# ublisterred_vow.net
KiCad netlist of a schematic drawn in EAGLE
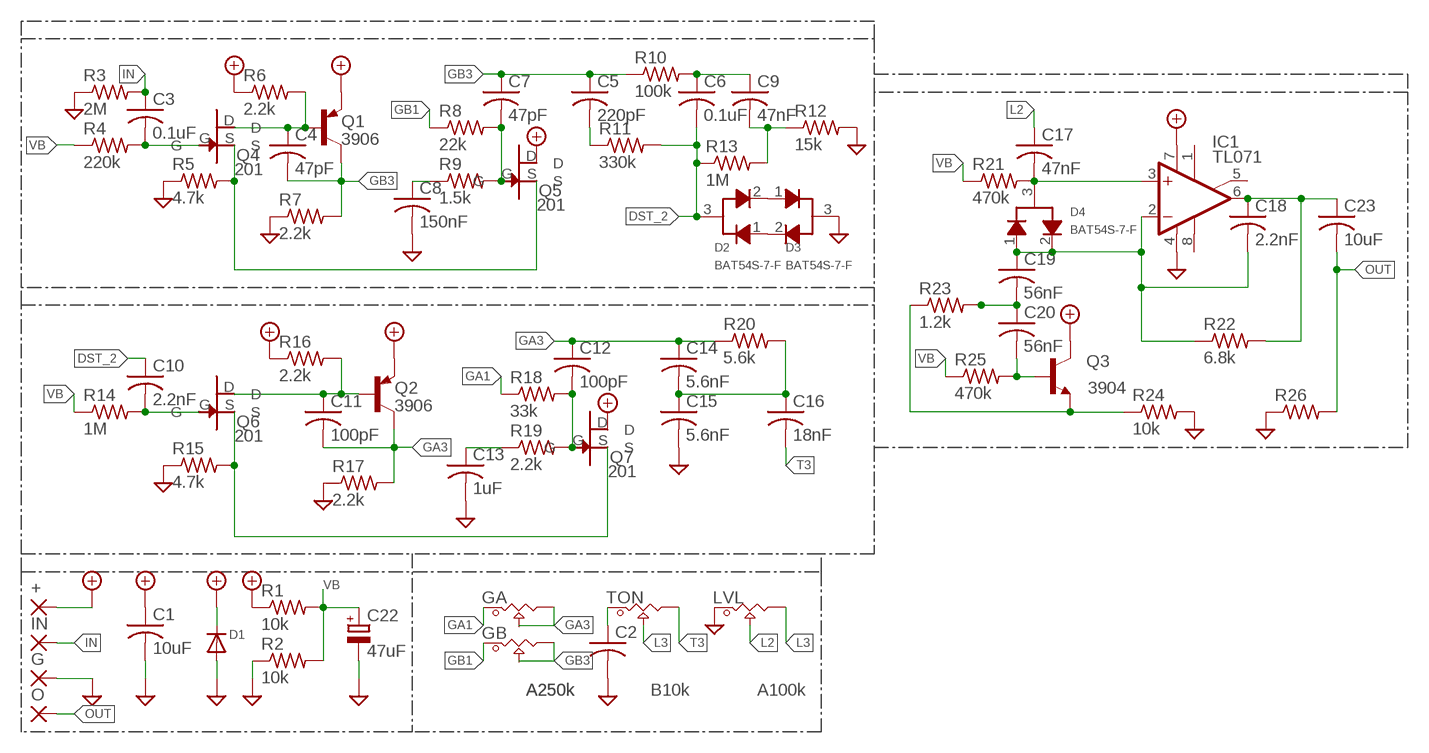
[diagram p0: schematic, sheet 1]

(export (version "E")
  (design (tool "Eeschema 10.0.6"))
  (components
    (comp (ref "+")
      (value "SMD2")
      (footprint "eagle-import:SMD1,27-2,54")
      (libsource (lib "eagle-import") (part "SMD2"))
    )
    (comp (ref "C1")
      (value "10uF")
      (footprint "eagle-import:C1206")
      (libsource (lib "eagle-import") (part "adafruit_420_C-USC1206"))
    )
    (comp (ref "C2")
      (value "C-USC0603")
      (footprint "eagle-import:C0603")
      (libsource (lib "eagle-import") (part "C-USC0603"))
    )
    (comp (ref "C3")
      (value "0.1uF")
      (footprint "eagle-import:C0603")
      (libsource (lib "eagle-import") (part "C-USC0603"))
    )
    (comp (ref "C4")
      (value "47pF")
      (footprint "eagle-import:C0603")
      (libsource (lib "eagle-import") (part "C-USC0603"))
    )
    (comp (ref "C5")
      (value "220pF")
      (footprint "eagle-import:C0603")
      (libsource (lib "eagle-import") (part "C-USC0603"))
    )
    (comp (ref "C6")
      (value "0.1uF")
      (footprint "eagle-import:C0603")
      (libsource (lib "eagle-import") (part "C-USC0603"))
    )
    (comp (ref "C7")
      (value "47pF")
      (footprint "eagle-import:C0603")
      (libsource (lib "eagle-import") (part "C-USC0603"))
    )
    (comp (ref "C8")
      (value "150nF")
      (footprint "eagle-import:C0603")
      (libsource (lib "eagle-import") (part "C-USC0603"))
    )
    (comp (ref "C9")
      (value "47nF")
      (footprint "eagle-import:C0603")
      (libsource (lib "eagle-import") (part "C-USC0603"))
    )
    (comp (ref "C10")
      (value "2.2nF")
      (footprint "eagle-import:C0603")
      (libsource (lib "eagle-import") (part "C-USC0603"))
    )
    (comp (ref "C11")
      (value "100pF")
      (footprint "eagle-import:C0603")
      (libsource (lib "eagle-import") (part "C-USC0603"))
    )
    (comp (ref "C12")
      (value "100pF")
      (footprint "eagle-import:C0603")
      (libsource (lib "eagle-import") (part "C-USC0603"))
    )
    (comp (ref "C13")
      (value "1uF")
      (footprint "eagle-import:C0603")
      (libsource (lib "eagle-import") (part "C-USC0603"))
    )
    (comp (ref "C14")
      (value "5.6nF")
      (footprint "eagle-import:C0603")
      (libsource (lib "eagle-import") (part "C-USC0603"))
    )
    (comp (ref "C15")
      (value "5.6nF")
      (footprint "eagle-import:C0603")
      (libsource (lib "eagle-import") (part "C-USC0603"))
    )
    (comp (ref "C16")
      (value "18nF")
      (footprint "eagle-import:C0603")
      (libsource (lib "eagle-import") (part "C-USC0603"))
    )
    (comp (ref "C17")
      (value "47nF")
      (footprint "eagle-import:C0603")
      (libsource (lib "eagle-import") (part "C-USC0603"))
    )
    (comp (ref "C18")
      (value "2.2nF")
      (footprint "eagle-import:C0603")
      (libsource (lib "eagle-import") (part "C-USC0603"))
    )
    (comp (ref "C19")
      (value "56nF")
      (footprint "eagle-import:C0603")
      (libsource (lib "eagle-import") (part "C-USC0603"))
    )
    (comp (ref "C20")
      (value "56nF")
      (footprint "eagle-import:C0603")
      (libsource (lib "eagle-import") (part "C-USC0603"))
    )
    (comp (ref "C22")
      (value "47uF")
      (footprint "eagle-import:CAPMP7343X310N")
      (libsource (lib "eagle-import") (part "C-POLTANTALUM-2917(7343-METRIC)_"))
    )
    (comp (ref "C23")
      (value "10uF")
      (footprint "eagle-import:C1206")
      (libsource (lib "eagle-import") (part "adafruit_420_C-USC1206"))
    )
    (comp (ref "D1")
      (value "DIODESOD-123")
      (footprint "eagle-import:SOD-123")
      (libsource (lib "eagle-import") (part "DIODESOD-123"))
    )
    (comp (ref "D2")
      (value "BAT54S-7-F")
      (footprint "eagle-import:SOT23-3")
      (fields
        (field (name "DIGIKEY_PART_NUMBER") "BAT54S-FDITR-ND")
        (field (name "MANUFACTURER") "Diodes Incorporated")
        (field (name "CREATED_BY") "PCBLayout.com")
      )
      (libsource (lib "eagle-import") (part "BAT54S-7-F"))
    )
    (comp (ref "D3")
      (value "BAT54S-7-F")
      (footprint "eagle-import:SOT23-3")
      (fields
        (field (name "DIGIKEY_PART_NUMBER") "BAT54S-FDITR-ND")
        (field (name "MANUFACTURER") "Diodes Incorporated")
        (field (name "CREATED_BY") "PCBLayout.com")
      )
      (libsource (lib "eagle-import") (part "BAT54S-7-F"))
    )
    (comp (ref "D4")
      (value "BAT54S-7-F")
      (footprint "eagle-import:SOT23-3")
      (fields
        (field (name "DIGIKEY_PART_NUMBER") "BAT54S-FDITR-ND")
        (field (name "MANUFACTURER") "Diodes Incorporated")
        (field (name "CREATED_BY") "PCBLayout.com")
      )
      (libsource (lib "eagle-import") (part "BAT54S-7-F"))
    )
    (comp (ref "G")
      (value "SMD2")
      (footprint "eagle-import:SMD1,27-2,54")
      (libsource (lib "eagle-import") (part "SMD2"))
    )
    (comp (ref "GA")
      (value "A250k")
      (footprint "eagle-import:POT_9MM_SMD")
      (libsource (lib "eagle-import") (part "POT_9MM_SMD"))
    )
    (comp (ref "GB")
      (value "A250k")
      (footprint "eagle-import:POT_9MM_SMD")
      (libsource (lib "eagle-import") (part "POT_9MM_SMD"))
    )
    (comp (ref "IC1")
      (value "TL071")
      (footprint "eagle-import:SO08")
      (libsource (lib "eagle-import") (part "TL071D"))
    )
    (comp (ref "IN")
      (value "SMD2")
      (footprint "eagle-import:SMD1,27-2,54")
      (libsource (lib "eagle-import") (part "SMD2"))
    )
    (comp (ref "LVL")
      (value "A100k")
      (footprint "eagle-import:POT_9MM_SMD")
      (libsource (lib "eagle-import") (part "POT_9MM_SMD"))
    )
    (comp (ref "O")
      (value "SMD2")
      (footprint "eagle-import:SMD1,27-2,54")
      (libsource (lib "eagle-import") (part "SMD2"))
    )
    (comp (ref "Q1")
      (value "3906")
      (footprint "eagle-import:SOT23-3")
      (fields
        (field (name "MANUFACTURER") "ON Semiconductor")
        (field (name "MPN") "MMBT3906LT1G")
        (field (name "CREATED_BY") "PCBLayout.com")
      )
      (libsource (lib "eagle-import") (part "MMBT3906LT1G"))
    )
    (comp (ref "Q2")
      (value "3906")
      (footprint "eagle-import:SOT23-3")
      (fields
        (field (name "MANUFACTURER") "ON Semiconductor")
        (field (name "MPN") "MMBT3906LT1G")
        (field (name "CREATED_BY") "PCBLayout.com")
      )
      (libsource (lib "eagle-import") (part "MMBT3906LT1G"))
    )
    (comp (ref "Q3")
      (value "3904")
      (footprint "eagle-import:SOT23-3")
      (fields
        (field (name "DIGIKEY_PART_NUMBER") "MMBT3904LT1GOSTR-ND")
        (field (name "MANUFACTURER") "ON Semiconductor")
        (field (name "MPN") "MMBT3904LT1G")
        (field (name "CREATED_BY") "PCBLayout.com")
      )
      (libsource (lib "eagle-import") (part "MMBT3904LT1G"))
    )
    (comp (ref "Q4")
      (value "201")
      (footprint "eagle-import:MMBFJ201")
      (libsource (lib "eagle-import") (part "MMBFJ201"))
    )
    (comp (ref "Q5")
      (value "201")
      (footprint "eagle-import:MMBFJ201")
      (libsource (lib "eagle-import") (part "MMBFJ201"))
    )
    (comp (ref "Q6")
      (value "201")
      (footprint "eagle-import:MMBFJ201")
      (libsource (lib "eagle-import") (part "MMBFJ201"))
    )
    (comp (ref "Q7")
      (value "201")
      (footprint "eagle-import:MMBFJ201")
      (libsource (lib "eagle-import") (part "MMBFJ201"))
    )
    (comp (ref "R1")
      (value "10k")
      (footprint "eagle-import:R0603")
      (libsource (lib "eagle-import") (part "R-US_R0603"))
    )
    (comp (ref "R2")
      (value "10k")
      (footprint "eagle-import:R0603")
      (libsource (lib "eagle-import") (part "R-US_R0603"))
    )
    (comp (ref "R3")
      (value "2M")
      (footprint "eagle-import:R0603")
      (libsource (lib "eagle-import") (part "R-US_R0603"))
    )
    (comp (ref "R4")
      (value "220k")
      (footprint "eagle-import:R0603")
      (libsource (lib "eagle-import") (part "R-US_R0603"))
    )
    (comp (ref "R5")
      (value "4.7k")
      (footprint "eagle-import:R0603")
      (libsource (lib "eagle-import") (part "R-US_R0603"))
    )
    (comp (ref "R6")
      (value "2.2k")
      (footprint "eagle-import:R0603")
      (libsource (lib "eagle-import") (part "R-US_R0603"))
    )
    (comp (ref "R7")
      (value "2.2k")
      (footprint "eagle-import:R0603")
      (libsource (lib "eagle-import") (part "R-US_R0603"))
    )
    (comp (ref "R8")
      (value "22k")
      (footprint "eagle-import:R0603")
      (libsource (lib "eagle-import") (part "R-US_R0603"))
    )
    (comp (ref "R9")
      (value "1.5k")
      (footprint "eagle-import:R0603")
      (libsource (lib "eagle-import") (part "R-US_R0603"))
    )
    (comp (ref "R10")
      (value "100k")
      (footprint "eagle-import:R0603")
      (libsource (lib "eagle-import") (part "R-US_R0603"))
    )
    (comp (ref "R11")
      (value "330k")
      (footprint "eagle-import:R0603")
      (libsource (lib "eagle-import") (part "R-US_R0603"))
    )
    (comp (ref "R12")
      (value "15k")
      (footprint "eagle-import:R0603")
      (libsource (lib "eagle-import") (part "R-US_R0603"))
    )
    (comp (ref "R13")
      (value "1M")
      (footprint "eagle-import:R0603")
      (libsource (lib "eagle-import") (part "R-US_R0603"))
    )
    (comp (ref "R14")
      (value "1M")
      (footprint "eagle-import:R0603")
      (libsource (lib "eagle-import") (part "R-US_R0603"))
    )
    (comp (ref "R15")
      (value "4.7k")
      (footprint "eagle-import:R0603")
      (libsource (lib "eagle-import") (part "R-US_R0603"))
    )
    (comp (ref "R16")
      (value "2.2k")
      (footprint "eagle-import:R0603")
      (libsource (lib "eagle-import") (part "R-US_R0603"))
    )
    (comp (ref "R17")
      (value "2.2k")
      (footprint "eagle-import:R0603")
      (libsource (lib "eagle-import") (part "R-US_R0603"))
    )
    (comp (ref "R18")
      (value "33k")
      (footprint "eagle-import:R0603")
      (libsource (lib "eagle-import") (part "R-US_R0603"))
    )
    (comp (ref "R19")
      (value "2.2k")
      (footprint "eagle-import:R0603")
      (libsource (lib "eagle-import") (part "R-US_R0603"))
    )
    (comp (ref "R20")
      (value "5.6k")
      (footprint "eagle-import:R0603")
      (libsource (lib "eagle-import") (part "R-US_R0603"))
    )
    (comp (ref "R21")
      (value "470k")
      (footprint "eagle-import:R0603")
      (libsource (lib "eagle-import") (part "R-US_R0603"))
    )
    (comp (ref "R22")
      (value "6.8k")
      (footprint "eagle-import:R0603")
      (libsource (lib "eagle-import") (part "R-US_R0603"))
    )
    (comp (ref "R23")
      (value "1.2k")
      (footprint "eagle-import:R0603")
      (libsource (lib "eagle-import") (part "R-US_R0603"))
    )
    (comp (ref "R24")
      (value "10k")
      (footprint "eagle-import:R0603")
      (libsource (lib "eagle-import") (part "R-US_R0603"))
    )
    (comp (ref "R25")
      (value "470k")
      (footprint "eagle-import:R0603")
      (libsource (lib "eagle-import") (part "R-US_R0603"))
    )
    (comp (ref "R26")
      (value "R-US_R0603")
      (footprint "eagle-import:R0603")
      (libsource (lib "eagle-import") (part "R-US_R0603"))
    )
    (comp (ref "TON")
      (value "B10k")
      (footprint "eagle-import:POT_9MM_SMD")
      (libsource (lib "eagle-import") (part "POT_9MM_SMD"))
    )
  )
  (nets
    (net (code "1") (name "+9V") (class "Default")
      (node (ref "+") (pin "1") (pinfunction "P_1") (pintype "passive"))
      (node (ref "C1") (pin "1") (pinfunction "1_1") (pintype "passive"))
      (node (ref "D1") (pin "C") (pinfunction "C_C") (pintype "passive"))
      (node (ref "IC1") (pin "7") (pinfunction "V+_7") (pintype "power_in"))
      (node (ref "Q1") (pin "2") (pinfunction "E_2") (pintype "passive"))
      (node (ref "Q2") (pin "2") (pinfunction "E_2") (pintype "passive"))
      (node (ref "Q3") (pin "3") (pinfunction "C_3") (pintype "passive"))
      (node (ref "Q5") (pin "D") (pinfunction "D_D") (pintype "bidirectional"))
      (node (ref "Q7") (pin "D") (pinfunction "D_D") (pintype "bidirectional"))
      (node (ref "R1") (pin "1") (pinfunction "1_1") (pintype "passive"))
      (node (ref "R16") (pin "1") (pinfunction "1_1") (pintype "passive"))
      (node (ref "R6") (pin "1") (pinfunction "1_1") (pintype "passive"))
    )
    (net (code "2") (name "DST_2") (class "Default")
      (node (ref "C10") (pin "1") (pinfunction "1_1") (pintype "passive"))
      (node (ref "C6") (pin "2") (pinfunction "2_2") (pintype "passive"))
      (node (ref "D2") (pin "3") (pinfunction "3_3") (pintype "passive"))
      (node (ref "R11") (pin "2") (pinfunction "2_2") (pintype "passive"))
      (node (ref "R13") (pin "1") (pinfunction "1_1") (pintype "passive"))
    )
    (net (code "3") (name "GA1") (class "Default")
      (node (ref "GA") (pin "1") (pinfunction "1_1") (pintype "bidirectional"))
      (node (ref "R18") (pin "1") (pinfunction "1_1") (pintype "passive"))
    )
    (net (code "4") (name "GA3") (class "Default")
      (node (ref "C11") (pin "2") (pinfunction "2_2") (pintype "passive"))
      (node (ref "C12") (pin "1") (pinfunction "1_1") (pintype "passive"))
      (node (ref "C14") (pin "1") (pinfunction "1_1") (pintype "passive"))
      (node (ref "GA") (pin "2") (pinfunction "2_2") (pintype "bidirectional"))
      (node (ref "GA") (pin "3") (pinfunction "3_3") (pintype "bidirectional"))
      (node (ref "Q2") (pin "3") (pinfunction "C_3") (pintype "passive"))
      (node (ref "R17") (pin "2") (pinfunction "2_2") (pintype "passive"))
      (node (ref "R20") (pin "1") (pinfunction "1_1") (pintype "passive"))
    )
    (net (code "5") (name "GB1") (class "Default")
      (node (ref "GB") (pin "1") (pinfunction "1_1") (pintype "bidirectional"))
      (node (ref "R8") (pin "1") (pinfunction "1_1") (pintype "passive"))
    )
    (net (code "6") (name "GB3") (class "Default")
      (node (ref "C4") (pin "2") (pinfunction "2_2") (pintype "passive"))
      (node (ref "C5") (pin "1") (pinfunction "1_1") (pintype "passive"))
      (node (ref "C7") (pin "1") (pinfunction "1_1") (pintype "passive"))
      (node (ref "GB") (pin "2") (pinfunction "2_2") (pintype "bidirectional"))
      (node (ref "GB") (pin "3") (pinfunction "3_3") (pintype "bidirectional"))
      (node (ref "Q1") (pin "3") (pinfunction "C_3") (pintype "passive"))
      (node (ref "R10") (pin "1") (pinfunction "1_1") (pintype "passive"))
      (node (ref "R7") (pin "2") (pinfunction "2_2") (pintype "passive"))
    )
    (net (code "7") (name "GND") (class "Default")
      (node (ref "C1") (pin "2") (pinfunction "2_2") (pintype "passive"))
      (node (ref "C13") (pin "2") (pinfunction "2_2") (pintype "passive"))
      (node (ref "C15") (pin "2") (pinfunction "2_2") (pintype "passive"))
      (node (ref "C2") (pin "2") (pinfunction "2_2") (pintype "passive"))
      (node (ref "C22") (pin "2") (pinfunction "-_2") (pintype "passive"))
      (node (ref "C8") (pin "2") (pinfunction "2_2") (pintype "passive"))
      (node (ref "D1") (pin "A") (pinfunction "A_A") (pintype "passive"))
      (node (ref "D3") (pin "3") (pinfunction "3_3") (pintype "passive"))
      (node (ref "G") (pin "1") (pinfunction "P_1") (pintype "passive"))
      (node (ref "IC1") (pin "4") (pinfunction "V-_4") (pintype "power_in"))
      (node (ref "LVL") (pin "1") (pinfunction "1_1") (pintype "bidirectional"))
      (node (ref "R12") (pin "2") (pinfunction "2_2") (pintype "passive"))
      (node (ref "R15") (pin "1") (pinfunction "1_1") (pintype "passive"))
      (node (ref "R17") (pin "1") (pinfunction "1_1") (pintype "passive"))
      (node (ref "R2") (pin "1") (pinfunction "1_1") (pintype "passive"))
      (node (ref "R24") (pin "2") (pinfunction "2_2") (pintype "passive"))
      (node (ref "R26") (pin "1") (pinfunction "1_1") (pintype "passive"))
      (node (ref "R3") (pin "1") (pinfunction "1_1") (pintype "passive"))
      (node (ref "R5") (pin "1") (pinfunction "1_1") (pintype "passive"))
      (node (ref "R7") (pin "1") (pinfunction "1_1") (pintype "passive"))
    )
    (net (code "8") (name "IN") (class "Default")
      (node (ref "C3") (pin "1") (pinfunction "1_1") (pintype "passive"))
      (node (ref "IN") (pin "1") (pinfunction "P_1") (pintype "passive"))
      (node (ref "R3") (pin "2") (pinfunction "2_2") (pintype "passive"))
    )
    (net (code "9") (name "L2") (class "Default")
      (node (ref "C17") (pin "1") (pinfunction "1_1") (pintype "passive"))
      (node (ref "LVL") (pin "2") (pinfunction "2_2") (pintype "bidirectional"))
    )
    (net (code "10") (name "L3") (class "Default")
      (node (ref "LVL") (pin "3") (pinfunction "3_3") (pintype "bidirectional"))
      (node (ref "TON") (pin "2") (pinfunction "2_2") (pintype "bidirectional"))
    )
    (net (code "11") (name "Net-(C2-Pad1)") (class "Default")
      (node (ref "C2") (pin "1") (pinfunction "1_1") (pintype "passive"))
      (node (ref "TON") (pin "1") (pinfunction "1_1") (pintype "bidirectional"))
    )
    (net (code "12") (name "Net-(C3-Pad2)") (class "Default")
      (node (ref "C3") (pin "2") (pinfunction "2_2") (pintype "passive"))
      (node (ref "Q4") (pin "G") (pinfunction "G_G") (pintype "bidirectional"))
      (node (ref "R4") (pin "2") (pinfunction "2_2") (pintype "passive"))
    )
    (net (code "13") (name "Net-(C5-Pad2)") (class "Default")
      (node (ref "C5") (pin "2") (pinfunction "2_2") (pintype "passive"))
      (node (ref "R11") (pin "1") (pinfunction "1_1") (pintype "passive"))
    )
    (net (code "14") (name "Net-(C6-Pad1)") (class "Default")
      (node (ref "C6") (pin "1") (pinfunction "1_1") (pintype "passive"))
      (node (ref "C9") (pin "1") (pinfunction "1_1") (pintype "passive"))
      (node (ref "R10") (pin "2") (pinfunction "2_2") (pintype "passive"))
    )
    (net (code "15") (name "Net-(C7-Pad2)") (class "Default")
      (node (ref "C7") (pin "2") (pinfunction "2_2") (pintype "passive"))
      (node (ref "Q5") (pin "G") (pinfunction "G_G") (pintype "bidirectional"))
      (node (ref "R8") (pin "2") (pinfunction "2_2") (pintype "passive"))
      (node (ref "R9") (pin "2") (pinfunction "2_2") (pintype "passive"))
    )
    (net (code "16") (name "Net-(C8-Pad1)") (class "Default")
      (node (ref "C8") (pin "1") (pinfunction "1_1") (pintype "passive"))
      (node (ref "R9") (pin "1") (pinfunction "1_1") (pintype "passive"))
    )
    (net (code "17") (name "Net-(C9-Pad2)") (class "Default")
      (node (ref "C9") (pin "2") (pinfunction "2_2") (pintype "passive"))
      (node (ref "R12") (pin "1") (pinfunction "1_1") (pintype "passive"))
      (node (ref "R13") (pin "2") (pinfunction "2_2") (pintype "passive"))
    )
    (net (code "18") (name "Net-(C10-Pad2)") (class "Default")
      (node (ref "C10") (pin "2") (pinfunction "2_2") (pintype "passive"))
      (node (ref "Q6") (pin "G") (pinfunction "G_G") (pintype "bidirectional"))
      (node (ref "R14") (pin "2") (pinfunction "2_2") (pintype "passive"))
    )
    (net (code "19") (name "Net-(C12-Pad2)") (class "Default")
      (node (ref "C12") (pin "2") (pinfunction "2_2") (pintype "passive"))
      (node (ref "Q7") (pin "G") (pinfunction "G_G") (pintype "bidirectional"))
      (node (ref "R18") (pin "2") (pinfunction "2_2") (pintype "passive"))
      (node (ref "R19") (pin "2") (pinfunction "2_2") (pintype "passive"))
    )
    (net (code "20") (name "Net-(C13-Pad1)") (class "Default")
      (node (ref "C13") (pin "1") (pinfunction "1_1") (pintype "passive"))
      (node (ref "R19") (pin "1") (pinfunction "1_1") (pintype "passive"))
    )
    (net (code "21") (name "Net-(C14-Pad2)") (class "Default")
      (node (ref "C14") (pin "2") (pinfunction "2_2") (pintype "passive"))
      (node (ref "C15") (pin "1") (pinfunction "1_1") (pintype "passive"))
      (node (ref "C16") (pin "1") (pinfunction "1_1") (pintype "passive"))
      (node (ref "R20") (pin "2") (pinfunction "2_2") (pintype "passive"))
    )
    (net (code "22") (name "Net-(C19-Pad2)") (class "Default")
      (node (ref "C19") (pin "2") (pinfunction "2_2") (pintype "passive"))
      (node (ref "C20") (pin "1") (pinfunction "1_1") (pintype "passive"))
      (node (ref "R23") (pin "2") (pinfunction "2_2") (pintype "passive"))
    )
    (net (code "23") (name "Net-(D2-Pad1)") (class "Default")
      (node (ref "D2") (pin "1") (pinfunction "1_1") (pintype "passive"))
      (node (ref "D3") (pin "2") (pinfunction "2_2") (pintype "passive"))
    )
    (net (code "24") (name "Net-(D2-Pad2)") (class "Default")
      (node (ref "D2") (pin "2") (pinfunction "2_2") (pintype "passive"))
      (node (ref "D3") (pin "1") (pinfunction "1_1") (pintype "passive"))
    )
    (net (code "25") (name "Net-(IC1-+IN)") (class "Default")
      (node (ref "C17") (pin "2") (pinfunction "2_2") (pintype "passive"))
      (node (ref "D4") (pin "3") (pinfunction "3_3") (pintype "passive"))
      (node (ref "IC1") (pin "3") (pinfunction "+IN_3") (pintype "input"))
      (node (ref "R21") (pin "2") (pinfunction "2_2") (pintype "passive"))
    )
    (net (code "26") (name "Net-(IC1--IN)") (class "Default")
      (node (ref "C18") (pin "2") (pinfunction "2_2") (pintype "passive"))
      (node (ref "C19") (pin "1") (pinfunction "1_1") (pintype "passive"))
      (node (ref "D4") (pin "1") (pinfunction "1_1") (pintype "passive"))
      (node (ref "D4") (pin "2") (pinfunction "2_2") (pintype "passive"))
      (node (ref "IC1") (pin "2") (pinfunction "-IN_2") (pintype "input"))
      (node (ref "R22") (pin "1") (pinfunction "1_1") (pintype "passive"))
    )
    (net (code "27") (name "Net-(IC1-OUT)") (class "Default")
      (node (ref "C18") (pin "1") (pinfunction "1_1") (pintype "passive"))
      (node (ref "C23") (pin "1") (pinfunction "1_1") (pintype "passive"))
      (node (ref "IC1") (pin "6") (pinfunction "OUT_6") (pintype "output"))
      (node (ref "R22") (pin "2") (pinfunction "2_2") (pintype "passive"))
    )
    (net (code "28") (name "Net-(Q1-B)") (class "Default")
      (node (ref "C4") (pin "1") (pinfunction "1_1") (pintype "passive"))
      (node (ref "Q1") (pin "1") (pinfunction "B_1") (pintype "passive"))
      (node (ref "Q4") (pin "D") (pinfunction "D_D") (pintype "bidirectional"))
      (node (ref "R6") (pin "2") (pinfunction "2_2") (pintype "passive"))
    )
    (net (code "29") (name "Net-(Q2-B)") (class "Default")
      (node (ref "C11") (pin "1") (pinfunction "1_1") (pintype "passive"))
      (node (ref "Q2") (pin "1") (pinfunction "B_1") (pintype "passive"))
      (node (ref "Q6") (pin "D") (pinfunction "D_D") (pintype "bidirectional"))
      (node (ref "R16") (pin "2") (pinfunction "2_2") (pintype "passive"))
    )
    (net (code "30") (name "Net-(Q3-B)") (class "Default")
      (node (ref "C20") (pin "2") (pinfunction "2_2") (pintype "passive"))
      (node (ref "Q3") (pin "1") (pinfunction "B_1") (pintype "passive"))
      (node (ref "R25") (pin "2") (pinfunction "2_2") (pintype "passive"))
    )
    (net (code "31") (name "Net-(Q3-E)") (class "Default")
      (node (ref "Q3") (pin "2") (pinfunction "E_2") (pintype "passive"))
      (node (ref "R23") (pin "1") (pinfunction "1_1") (pintype "passive"))
      (node (ref "R24") (pin "1") (pinfunction "1_1") (pintype "passive"))
    )
    (net (code "32") (name "Net-(Q4-PadS)") (class "Default")
      (node (ref "Q4") (pin "S") (pinfunction "S_S") (pintype "bidirectional"))
      (node (ref "Q5") (pin "S") (pinfunction "S_S") (pintype "bidirectional"))
      (node (ref "R5") (pin "2") (pinfunction "2_2") (pintype "passive"))
    )
    (net (code "33") (name "Net-(Q6-PadS)") (class "Default")
      (node (ref "Q6") (pin "S") (pinfunction "S_S") (pintype "bidirectional"))
      (node (ref "Q7") (pin "S") (pinfunction "S_S") (pintype "bidirectional"))
      (node (ref "R15") (pin "2") (pinfunction "2_2") (pintype "passive"))
    )
    (net (code "34") (name "OUT") (class "Default")
      (node (ref "C23") (pin "2") (pinfunction "2_2") (pintype "passive"))
      (node (ref "O") (pin "1") (pinfunction "P_1") (pintype "passive"))
      (node (ref "R26") (pin "2") (pinfunction "2_2") (pintype "passive"))
    )
    (net (code "35") (name "T3") (class "Default")
      (node (ref "C16") (pin "2") (pinfunction "2_2") (pintype "passive"))
      (node (ref "TON") (pin "3") (pinfunction "3_3") (pintype "bidirectional"))
    )
    (net (code "36") (name "VB") (class "Default")
      (node (ref "C22") (pin "1") (pinfunction "+_1") (pintype "passive"))
      (node (ref "R1") (pin "2") (pinfunction "2_2") (pintype "passive"))
      (node (ref "R14") (pin "1") (pinfunction "1_1") (pintype "passive"))
      (node (ref "R2") (pin "2") (pinfunction "2_2") (pintype "passive"))
      (node (ref "R21") (pin "1") (pinfunction "1_1") (pintype "passive"))
      (node (ref "R25") (pin "1") (pinfunction "1_1") (pintype "passive"))
      (node (ref "R4") (pin "1") (pinfunction "1_1") (pintype "passive"))
    )
    (net (code "37") (name "unconnected-(IC1-ON1-Pad1)") (class "Default")
      (node (ref "IC1") (pin "1") (pinfunction "ON1_1") (pintype "passive"))
    )
    (net (code "38") (name "unconnected-(IC1-ON2-Pad5)") (class "Default")
      (node (ref "IC1") (pin "5") (pinfunction "ON2_5") (pintype "passive"))
    )
    (net (code "39") (name "unconnected-(IC1-OPT-Pad8)") (class "Default")
      (node (ref "IC1") (pin "8") (pinfunction "OPT_8") (pintype "passive"))
    )
  )
)
